# sch.net
KiCad netlist of a schematic drawn in Altium Designer
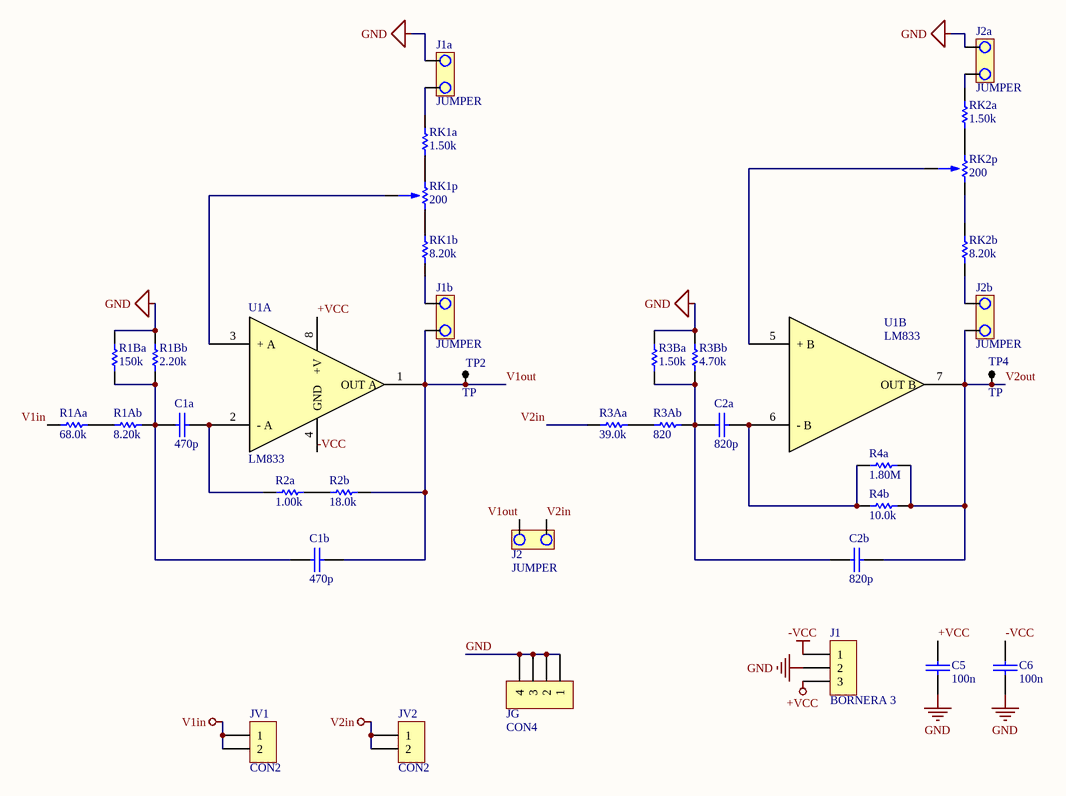
[diagram p0: sch.SchDoc]

(export (version "E")
  (design (tool "Eeschema 10.0.6"))
  (components
    (comp (ref "C1a") (value "470p") (footprint "CAP100") (libsource (lib "LIBEBAL") (part "CAP")))
    (comp (ref "C1b") (value "470p") (footprint "CAP100") (libsource (lib "LIBEBAL") (part "CAP")))
    (comp (ref "C2a") (value "820p") (footprint "CAP100") (libsource (lib "LIBEBAL") (part "CAP")))
    (comp (ref "C2b") (value "820p") (footprint "CAP100") (libsource (lib "LIBEBAL") (part "CAP")))
    (comp (ref "C5") (value "100n") (footprint "CAP100") (libsource (lib "LIBEBAL") (part "CAP")))
    (comp (ref "C6") (value "100n") (footprint "CAP200") (libsource (lib "LIBEBAL") (part "CAP")))
    (comp (ref "J1")
      (value "BORNERA 3")
      (footprint "BORNERA3")
      (libsource (lib "LIBEBAL") (part "BORNERA 3"))
    )
    (comp (ref "J1a") (value "JUMPER") (footprint "JUMPER2") (libsource (lib "LIBEBAL") (part "JUMPER")))
    (comp (ref "J1b") (value "JUMPER") (footprint "JUMPER2") (libsource (lib "LIBEBAL") (part "JUMPER")))
    (comp (ref "J2") (value "JUMPER") (footprint "JUMPER2") (libsource (lib "") (part "JUMPER_1")))
    (comp (ref "J2a") (value "JUMPER") (footprint "JUMPER2") (libsource (lib "LIBEBAL") (part "JUMPER")))
    (comp (ref "J2b") (value "JUMPER") (footprint "JUMPER2") (libsource (lib "LIBEBAL") (part "JUMPER")))
    (comp (ref "JG") (value "CON4") (footprint "SIP4") (libsource (lib "LIBEBAL") (part "CON4")))
    (comp (ref "JV1") (value "CON2") (footprint "SIP2") (libsource (lib "LIBEBAL") (part "CON2")))
    (comp (ref "JV2") (value "CON2") (footprint "SIP2") (libsource (lib "LIBEBAL") (part "CON2")))
    (comp (ref "R1Aa") (value "68.0k") (footprint "0805") (libsource (lib "LIBEBAL") (part "RES")))
    (comp (ref "R1Ab") (value "8.20k") (footprint "0805") (libsource (lib "LIBEBAL") (part "RES")))
    (comp (ref "R1Ba") (value "150k") (footprint "0805") (libsource (lib "LIBEBAL") (part "RES")))
    (comp (ref "R1Bb") (value "2.20k") (footprint "0805") (libsource (lib "LIBEBAL") (part "RES")))
    (comp (ref "R2a") (value "1.00k") (footprint "0805") (libsource (lib "LIBEBAL") (part "RES")))
    (comp (ref "R2b") (value "18.0k") (footprint "0805") (libsource (lib "LIBEBAL") (part "RES")))
    (comp (ref "R3Aa") (value "39.0k") (footprint "0805") (libsource (lib "LIBEBAL") (part "RES")))
    (comp (ref "R3Ab") (value "820") (footprint "0805") (libsource (lib "LIBEBAL") (part "RES")))
    (comp (ref "R3Ba") (value "1.50k") (footprint "0805") (libsource (lib "LIBEBAL") (part "RES")))
    (comp (ref "R3Bb") (value "4.70k") (footprint "0805") (libsource (lib "LIBEBAL") (part "RES")))
    (comp (ref "R4a") (value "1.80M") (footprint "RES500") (libsource (lib "LIBEBAL") (part "RES")))
    (comp (ref "R4b") (value "10.0k") (footprint "0805") (libsource (lib "LIBEBAL") (part "RES")))
    (comp (ref "RK1a") (value "1.50k") (footprint "0805") (libsource (lib "LIBEBAL") (part "RES")))
    (comp (ref "RK1b") (value "8.20k") (footprint "0805") (libsource (lib "LIBEBAL") (part "RES")))
    (comp (ref "RK1p") (value "200") (footprint "PRESET V") (libsource (lib "LIBEBAL") (part "PRESET")))
    (comp (ref "RK2a") (value "1.50k") (footprint "0805") (libsource (lib "LIBEBAL") (part "RES")))
    (comp (ref "RK2b") (value "8.20k") (footprint "0805") (libsource (lib "LIBEBAL") (part "RES")))
    (comp (ref "RK2p") (value "200") (footprint "PRESET V") (libsource (lib "LIBEBAL") (part "PRESET")))
    (comp (ref "TP2") (value "TP") (footprint "TPTH") (libsource (lib "LIBEBAL") (part "TP")))
    (comp (ref "TP4") (value "TP") (footprint "TPTH") (libsource (lib "LIBEBAL") (part "TP")))
    (comp (ref "U1")
      (value "LM833")
      (footprint "DIP8")
      (description "Dual Audio Operational Amplifier")
      (libsource (lib "LIBEBAL") (part "LM833"))
    )
  )
  (nets
    (net (code "1") (name "+VCC") (class "Default")
      (node (ref "C5") (pin "1") (pinfunction "1_1") (pintype "passive"))
      (node (ref "J1") (pin "3") (pinfunction "3_3") (pintype "passive"))
      (node (ref "U1") (pin "8") (pinfunction "+V_8") (pintype "passive"))
    )
    (net (code "2") (name "-VCC") (class "Default")
      (node (ref "C6") (pin "1") (pinfunction "1_1") (pintype "passive"))
      (node (ref "J1") (pin "1") (pinfunction "1_1") (pintype "passive"))
      (node (ref "U1") (pin "4") (pinfunction "GND_4") (pintype "passive"))
    )
    (net (code "3") (name "/V1out") (class "Default")
      (node (ref "C1b") (pin "1") (pinfunction "1_1") (pintype "passive"))
      (node (ref "J1b") (pin "1") (pinfunction "1_1") (pintype "passive"))
      (node (ref "J2") (pin "1") (pinfunction "1_1") (pintype "passive"))
      (node (ref "R2b") (pin "2") (pinfunction "2_2") (pintype "passive"))
      (node (ref "TP2") (pin "1") (pinfunction "1_1") (pintype "passive"))
      (node (ref "U1") (pin "1") (pinfunction "OUT_A_1") (pintype "passive"))
    )
    (net (code "4") (name "/V2out") (class "Default")
      (node (ref "C2b") (pin "1") (pinfunction "1_1") (pintype "passive"))
      (node (ref "J2b") (pin "1") (pinfunction "1_1") (pintype "passive"))
      (node (ref "R4a") (pin "2") (pinfunction "2_2") (pintype "passive"))
      (node (ref "R4b") (pin "2") (pinfunction "2_2") (pintype "passive"))
      (node (ref "TP4") (pin "1") (pinfunction "1_1") (pintype "passive"))
      (node (ref "U1") (pin "7") (pinfunction "OUT_B_7") (pintype "passive"))
    )
    (net (code "5") (name "GND") (class "Default")
      (node (ref "C5") (pin "2") (pinfunction "2_2") (pintype "passive"))
      (node (ref "C6") (pin "2") (pinfunction "2_2") (pintype "passive"))
      (node (ref "J1") (pin "2") (pinfunction "2_2") (pintype "passive"))
      (node (ref "J1a") (pin "2") (pinfunction "2_2") (pintype "passive"))
      (node (ref "J2a") (pin "2") (pinfunction "2_2") (pintype "passive"))
      (node (ref "JG") (pin "1") (pinfunction "1_1") (pintype "passive"))
      (node (ref "JG") (pin "2") (pinfunction "2_2") (pintype "passive"))
      (node (ref "JG") (pin "3") (pinfunction "3_3") (pintype "passive"))
      (node (ref "JG") (pin "4") (pinfunction "4_4") (pintype "passive"))
      (node (ref "R1Ba") (pin "1") (pinfunction "1_1") (pintype "passive"))
      (node (ref "R1Bb") (pin "1") (pinfunction "1_1") (pintype "passive"))
      (node (ref "R3Ba") (pin "1") (pinfunction "1_1") (pintype "passive"))
      (node (ref "R3Bb") (pin "1") (pinfunction "1_1") (pintype "passive"))
    )
    (net (code "6") (name "Net-(C1a-Pad2)") (class "Default")
      (node (ref "C1a") (pin "2") (pinfunction "2_2") (pintype "passive"))
      (node (ref "C1b") (pin "2") (pinfunction "2_2") (pintype "passive"))
      (node (ref "R1Ab") (pin "2") (pinfunction "2_2") (pintype "passive"))
      (node (ref "R1Ba") (pin "2") (pinfunction "2_2") (pintype "passive"))
      (node (ref "R1Bb") (pin "2") (pinfunction "2_2") (pintype "passive"))
    )
    (net (code "7") (name "Net-(C2a-Pad2)") (class "Default")
      (node (ref "C2a") (pin "2") (pinfunction "2_2") (pintype "passive"))
      (node (ref "C2b") (pin "2") (pinfunction "2_2") (pintype "passive"))
      (node (ref "R3Ab") (pin "2") (pinfunction "2_2") (pintype "passive"))
      (node (ref "R3Ba") (pin "2") (pinfunction "2_2") (pintype "passive"))
      (node (ref "R3Bb") (pin "2") (pinfunction "2_2") (pintype "passive"))
    )
    (net (code "8") (name "Net-(J1a-Pad1)") (class "Default")
      (node (ref "J1a") (pin "1") (pinfunction "1_1") (pintype "passive"))
      (node (ref "RK1a") (pin "1") (pinfunction "1_1") (pintype "passive"))
    )
    (net (code "9") (name "Net-(J1b-Pad2)") (class "Default")
      (node (ref "J1b") (pin "2") (pinfunction "2_2") (pintype "passive"))
      (node (ref "RK1b") (pin "2") (pinfunction "2_2") (pintype "passive"))
    )
    (net (code "10") (name "Net-(J2a-Pad1)") (class "Default")
      (node (ref "J2a") (pin "1") (pinfunction "1_1") (pintype "passive"))
      (node (ref "RK2a") (pin "1") (pinfunction "1_1") (pintype "passive"))
    )
    (net (code "11") (name "Net-(J2b-Pad2)") (class "Default")
      (node (ref "J2b") (pin "2") (pinfunction "2_2") (pintype "passive"))
      (node (ref "RK2b") (pin "2") (pinfunction "2_2") (pintype "passive"))
    )
    (net (code "12") (name "Net-(R1Aa-Pad2)") (class "Default")
      (node (ref "R1Aa") (pin "2") (pinfunction "2_2") (pintype "passive"))
      (node (ref "R1Ab") (pin "1") (pinfunction "1_1") (pintype "passive"))
    )
    (net (code "13") (name "Net-(R2a-Pad2)") (class "Default")
      (node (ref "R2a") (pin "2") (pinfunction "2_2") (pintype "passive"))
      (node (ref "R2b") (pin "1") (pinfunction "1_1") (pintype "passive"))
    )
    (net (code "14") (name "Net-(R3Aa-Pad2)") (class "Default")
      (node (ref "R3Aa") (pin "2") (pinfunction "2_2") (pintype "passive"))
      (node (ref "R3Ab") (pin "1") (pinfunction "1_1") (pintype "passive"))
    )
    (net (code "15") (name "Net-(RK1a-Pad2)") (class "Default")
      (node (ref "RK1a") (pin "2") (pinfunction "2_2") (pintype "passive"))
      (node (ref "RK1p") (pin "3") (pinfunction "3_3") (pintype "passive"))
    )
    (net (code "16") (name "Net-(RK1b-Pad1)") (class "Default")
      (node (ref "RK1b") (pin "1") (pinfunction "1_1") (pintype "passive"))
      (node (ref "RK1p") (pin "1") (pinfunction "1_1") (pintype "passive"))
    )
    (net (code "17") (name "Net-(RK2a-Pad2)") (class "Default")
      (node (ref "RK2a") (pin "2") (pinfunction "2_2") (pintype "passive"))
      (node (ref "RK2p") (pin "3") (pinfunction "3_3") (pintype "passive"))
    )
    (net (code "18") (name "Net-(RK2b-Pad1)") (class "Default")
      (node (ref "RK2b") (pin "1") (pinfunction "1_1") (pintype "passive"))
      (node (ref "RK2p") (pin "1") (pinfunction "1_1") (pintype "passive"))
    )
    (net (code "19") (name "Net-(U1A-+_A)") (class "Default")
      (node (ref "RK1p") (pin "2") (pinfunction "2_2") (pintype "passive"))
      (node (ref "U1") (pin "3") (pinfunction "+_A_3") (pintype "passive"))
    )
    (net (code "20") (name "Net-(U1A--_A)") (class "Default")
      (node (ref "C1a") (pin "1") (pinfunction "1_1") (pintype "passive"))
      (node (ref "R2a") (pin "1") (pinfunction "1_1") (pintype "passive"))
      (node (ref "U1") (pin "2") (pinfunction "-_A_2") (pintype "passive"))
    )
    (net (code "21") (name "Net-(U1B-+_B)") (class "Default")
      (node (ref "RK2p") (pin "2") (pinfunction "2_2") (pintype "passive"))
      (node (ref "U1") (pin "5") (pinfunction "+_B_5") (pintype "passive"))
    )
    (net (code "22") (name "Net-(U1B--_B)") (class "Default")
      (node (ref "C2a") (pin "1") (pinfunction "1_1") (pintype "passive"))
      (node (ref "R4a") (pin "1") (pinfunction "1_1") (pintype "passive"))
      (node (ref "R4b") (pin "1") (pinfunction "1_1") (pintype "passive"))
      (node (ref "U1") (pin "6") (pinfunction "-_B_6") (pintype "passive"))
    )
    (net (code "23") (name "V1in") (class "Default")
      (node (ref "JV1") (pin "1") (pinfunction "1_1") (pintype "passive"))
      (node (ref "JV1") (pin "2") (pinfunction "2_2") (pintype "passive"))
      (node (ref "R1Aa") (pin "1") (pinfunction "1_1") (pintype "passive"))
    )
    (net (code "24") (name "V2in") (class "Default")
      (node (ref "J2") (pin "2") (pinfunction "2_2") (pintype "passive"))
      (node (ref "JV2") (pin "1") (pinfunction "1_1") (pintype "passive"))
      (node (ref "JV2") (pin "2") (pinfunction "2_2") (pintype "passive"))
      (node (ref "R3Aa") (pin "1") (pinfunction "1_1") (pintype "passive"))
    )
  )
)
